# DS2502_prog.net
KiCad netlist of a schematic drawn in EAGLE
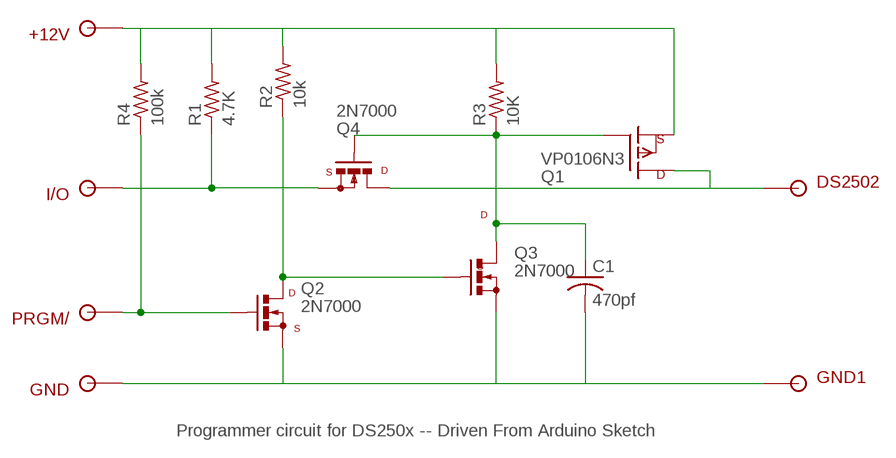
[diagram p0: schematic, sheet 1]

(export (version "E")
  (design (tool "Eeschema 10.0.6"))
  (components
    (comp (ref "+12V")
      (value "SOLDER_POINTA")
      (footprint "eagle-import:P1-13")
      (libsource (lib "eagle-import") (part "SOLDER_POINTA"))
    )
    (comp (ref "C1")
      (value "470pf")
      (footprint "eagle-import:C025-025X050")
      (libsource (lib "eagle-import") (part "C-US025-025X050"))
    )
    (comp (ref "DS2502")
      (value "SOLDER_POINTA")
      (footprint "eagle-import:P1-13")
      (libsource (lib "eagle-import") (part "SOLDER_POINTA"))
    )
    (comp (ref "GND")
      (value "SOLDER_POINTA")
      (footprint "eagle-import:P1-13")
      (libsource (lib "eagle-import") (part "SOLDER_POINTA"))
    )
    (comp (ref "GND1")
      (value "SOLDER_POINTA")
      (footprint "eagle-import:P1-13")
      (libsource (lib "eagle-import") (part "SOLDER_POINTA"))
    )
    (comp (ref "I/O")
      (value "SOLDER_POINTA")
      (footprint "eagle-import:P1-13")
      (libsource (lib "eagle-import") (part "SOLDER_POINTA"))
    )
    (comp (ref "PRGM/")
      (value "SOLDER_POINTA")
      (footprint "eagle-import:P1-13")
      (libsource (lib "eagle-import") (part "SOLDER_POINTA"))
    )
    (comp (ref "Q1")
      (value "VP0106N3")
      (footprint "eagle-import:TO92-")
      (libsource (lib "eagle-import") (part "BSS110TO920"))
    )
    (comp (ref "Q2")
      (value "2N7000")
      (footprint "eagle-import:TO92-LINE")
      (libsource (lib "eagle-import") (part "BS170T092-"))
    )
    (comp (ref "Q3")
      (value "2N7000")
      (footprint "eagle-import:TO92-LINE")
      (libsource (lib "eagle-import") (part "BS170T092-"))
    )
    (comp (ref "Q4")
      (value "2N7000")
      (footprint "eagle-import:TO92-LINE")
      (libsource (lib "eagle-import") (part "BS170T092-"))
    )
    (comp (ref "R1")
      (value "4.7K")
      (footprint "eagle-import:0207_2V")
      (libsource (lib "eagle-import") (part "R-US_0207/2V"))
    )
    (comp (ref "R2")
      (value "10k")
      (footprint "eagle-import:0309_10")
      (libsource (lib "eagle-import") (part "R-US_0309/10"))
    )
    (comp (ref "R3")
      (value "10K")
      (footprint "eagle-import:0207_2V")
      (libsource (lib "eagle-import") (part "R-US_0207/2V"))
    )
    (comp (ref "R4")
      (value "100k")
      (footprint "eagle-import:0309_10")
      (libsource (lib "eagle-import") (part "R-US_0309/10"))
    )
  )
  (nets
    (net (code "1") (name "Net-(+12V-P$1)") (class "Default")
      (node (ref "+12V") (pin "1") (pinfunction "P$1_1") (pintype "bidirectional"))
      (node (ref "Q1") (pin "3") (pinfunction "S_3") (pintype "passive"))
      (node (ref "R1") (pin "2") (pinfunction "2_2") (pintype "passive"))
      (node (ref "R2") (pin "2") (pinfunction "2_2") (pintype "passive"))
      (node (ref "R3") (pin "2") (pinfunction "2_2") (pintype "passive"))
      (node (ref "R4") (pin "2") (pinfunction "2_2") (pintype "passive"))
    )
    (net (code "2") (name "Net-(DS2502-P$1)") (class "Default")
      (node (ref "DS2502") (pin "1") (pinfunction "P$1_1") (pintype "bidirectional"))
      (node (ref "Q1") (pin "1") (pinfunction "D_1") (pintype "passive"))
      (node (ref "Q4") (pin "1") (pinfunction "D_1") (pintype "passive"))
    )
    (net (code "3") (name "Net-(GND-P$1)") (class "Default")
      (node (ref "C1") (pin "2") (pinfunction "2_2") (pintype "passive"))
      (node (ref "GND") (pin "1") (pinfunction "P$1_1") (pintype "bidirectional"))
      (node (ref "GND1") (pin "1") (pinfunction "P$1_1") (pintype "bidirectional"))
      (node (ref "Q2") (pin "3") (pinfunction "S_3") (pintype "passive"))
      (node (ref "Q3") (pin "3") (pinfunction "S_3") (pintype "passive"))
    )
    (net (code "4") (name "Net-(I/O-P$1)") (class "Default")
      (node (ref "I/O") (pin "1") (pinfunction "P$1_1") (pintype "bidirectional"))
      (node (ref "Q4") (pin "3") (pinfunction "S_3") (pintype "passive"))
      (node (ref "R1") (pin "1") (pinfunction "1_1") (pintype "passive"))
    )
    (net (code "5") (name "Net-(PRGM/-P$1)") (class "Default")
      (node (ref "PRGM/") (pin "1") (pinfunction "P$1_1") (pintype "bidirectional"))
      (node (ref "Q2") (pin "2") (pinfunction "G_2") (pintype "passive"))
      (node (ref "R4") (pin "1") (pinfunction "1_1") (pintype "passive"))
    )
    (net (code "6") (name "Net-(Q1-G)") (class "Default")
      (node (ref "C1") (pin "1") (pinfunction "1_1") (pintype "passive"))
      (node (ref "Q1") (pin "2") (pinfunction "G_2") (pintype "passive"))
      (node (ref "Q3") (pin "1") (pinfunction "D_1") (pintype "passive"))
      (node (ref "Q4") (pin "2") (pinfunction "G_2") (pintype "passive"))
      (node (ref "R3") (pin "1") (pinfunction "1_1") (pintype "passive"))
    )
    (net (code "7") (name "Net-(Q2-D)") (class "Default")
      (node (ref "Q2") (pin "1") (pinfunction "D_1") (pintype "passive"))
      (node (ref "Q3") (pin "2") (pinfunction "G_2") (pintype "passive"))
      (node (ref "R2") (pin "1") (pinfunction "1_1") (pintype "passive"))
    )
  )
)
